# zumy_carrier_board.net
KiCad netlist of a schematic drawn in EAGLE
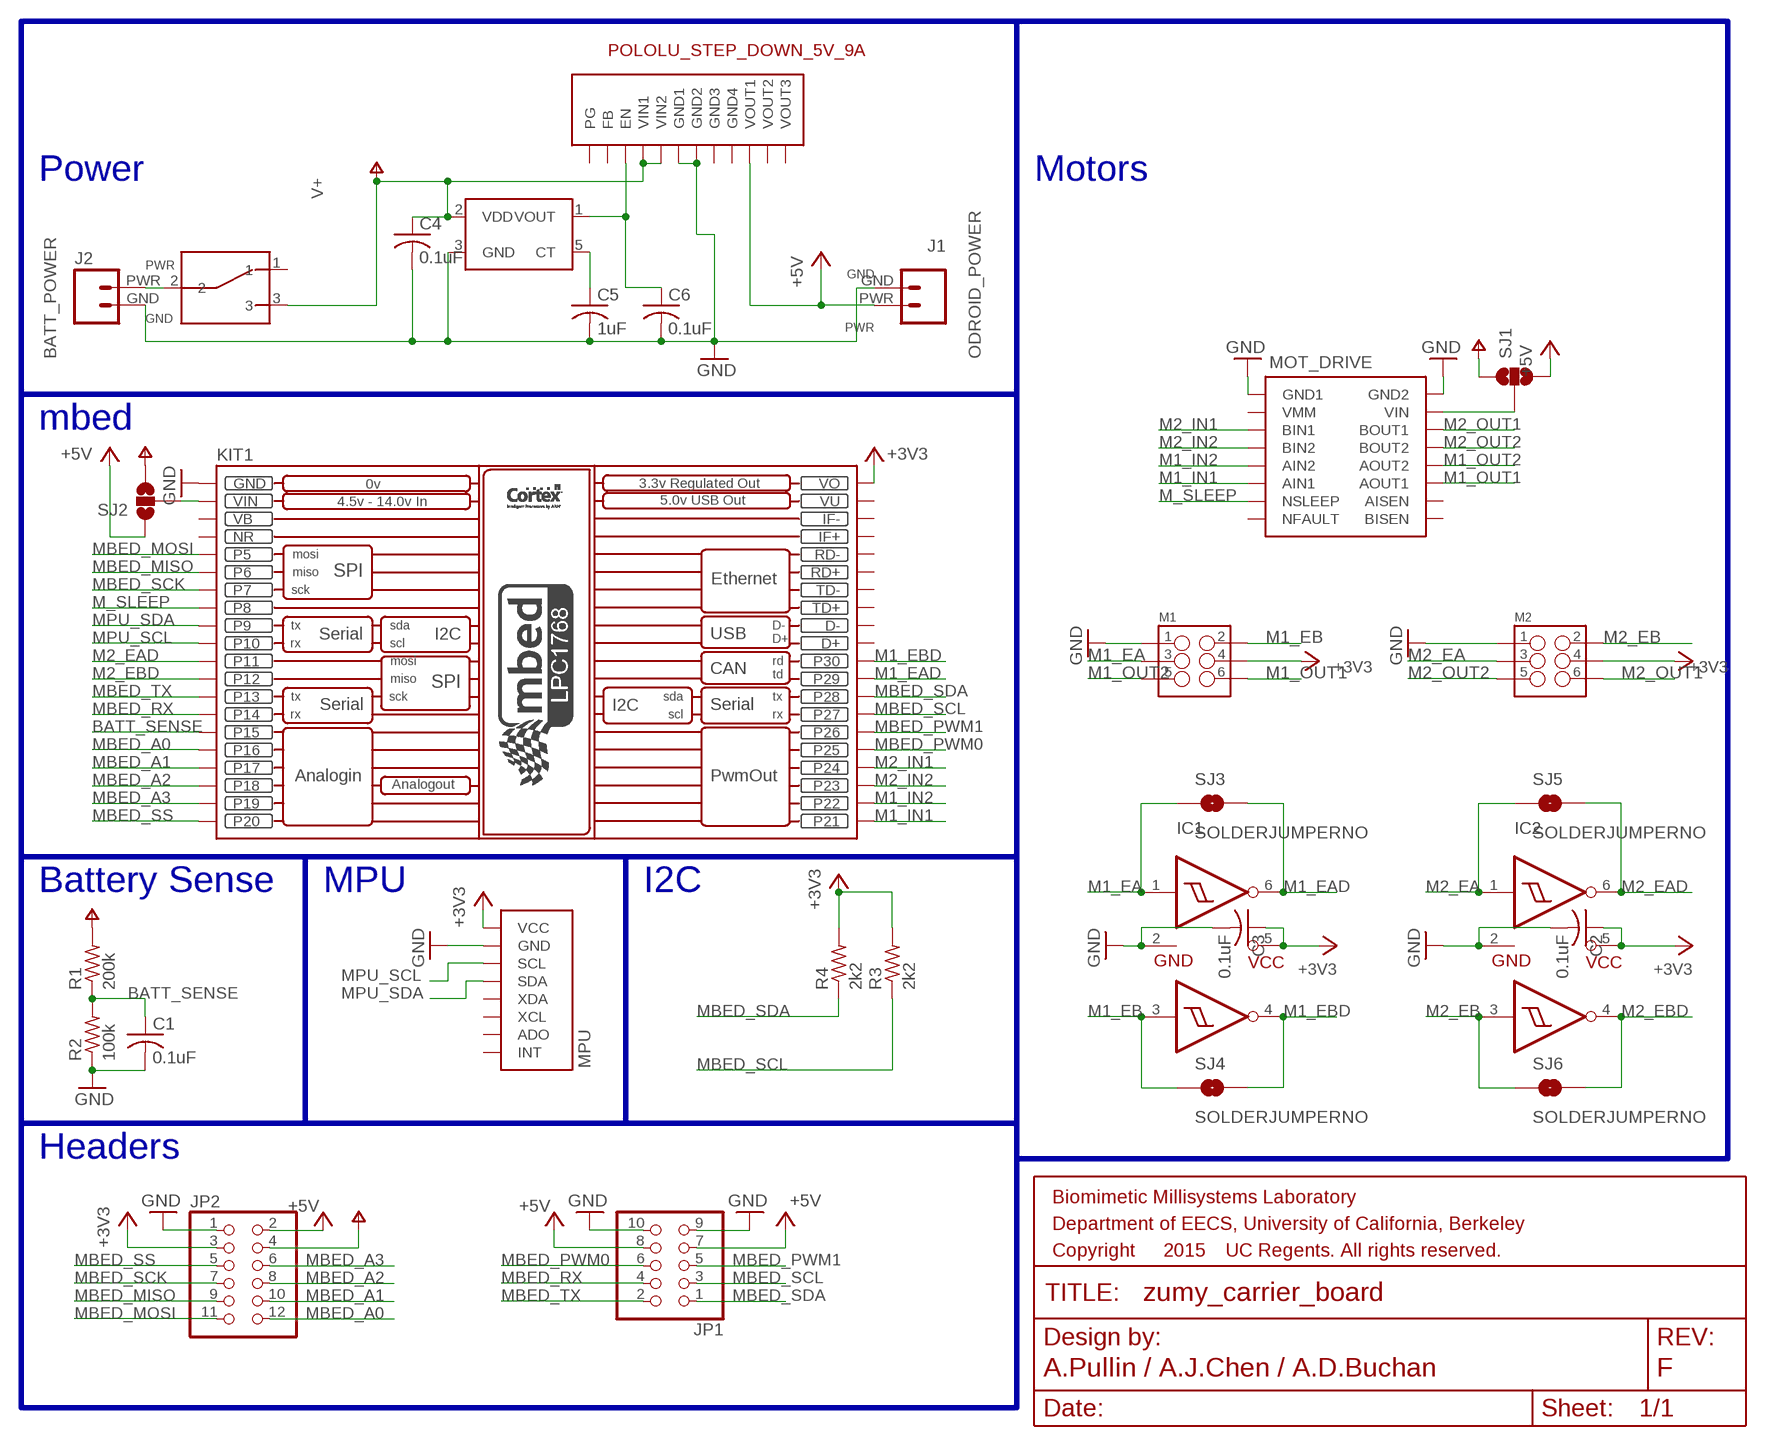
[diagram p0: schematic, sheet 1]

(export (version "E")
  (design (tool "Eeschema 10.0.6"))
  (components
    (comp (ref "C1")
      (value "0.1uF")
      (footprint "eagle-import:C1206")
      (libsource (lib "eagle-import") (part "C-USC1206"))
    )
    (comp (ref "C2")
      (value "0.1uF")
      (footprint "eagle-import:C1206")
      (libsource (lib "eagle-import") (part "C-USC1206"))
    )
    (comp (ref "C3")
      (value "0.1uF")
      (footprint "eagle-import:C1206")
      (libsource (lib "eagle-import") (part "C-USC1206"))
    )
    (comp (ref "C4")
      (value "0.1uF")
      (footprint "eagle-import:C1206")
      (libsource (lib "eagle-import") (part "C-USC1206"))
    )
    (comp (ref "C5")
      (value "1uF")
      (footprint "eagle-import:C1206")
      (libsource (lib "eagle-import") (part "C-USC1206"))
    )
    (comp (ref "C6")
      (value "0.1uF")
      (footprint "eagle-import:C1206")
      (libsource (lib "eagle-import") (part "C-USC1206"))
    )
    (comp (ref "IC1")
      (value "SN74AUP2G17")
      (footprint "eagle-import:SC-70-6")
      (libsource (lib "eagle-import") (part "SN74AUP2G17"))
    )
    (comp (ref "IC2")
      (value "SN74AUP2G17")
      (footprint "eagle-import:SC-70-6")
      (libsource (lib "eagle-import") (part "SN74AUP2G17"))
    )
    (comp (ref "J1")
      (value "ODROID_POWER")
      (footprint "eagle-import:ODOIRD_PWR")
      (libsource (lib "eagle-import") (part "ODROID_POWER"))
    )
    (comp (ref "J2")
      (value "BATT_POWER")
      (footprint "eagle-import:BATT_POWER")
      (libsource (lib "eagle-import") (part "BATT_POWER"))
    )
    (comp (ref "JP1")
      (value "PINHD-2X5")
      (footprint "eagle-import:2X05")
      (libsource (lib "eagle-import") (part "PINHD-2X5"))
    )
    (comp (ref "JP2")
      (value "PINHD-2X6")
      (footprint "eagle-import:2X06")
      (libsource (lib "eagle-import") (part "PINHD-2X6"))
    )
    (comp (ref "KIT1")
      (value "MBED_NXP_LPC1768")
      (footprint "eagle-import:MBED-KIT")
      (libsource (lib "eagle-import") (part "MBED_NXP_LPC1768"))
    )
    (comp (ref "M1")
      (value "M03X2SHROUD")
      (footprint "eagle-import:2X3-SHROUDED")
      (libsource (lib "eagle-import") (part "M03X2SHROUD"))
    )
    (comp (ref "M2")
      (value "M03X2SHROUD")
      (footprint "eagle-import:2X3-SHROUDED")
      (libsource (lib "eagle-import") (part "M03X2SHROUD"))
    )
    (comp (ref "MOT_DRIVE")
      (value "POLOLU_DRV8833_MODULE")
      (footprint "eagle-import:POLOLU_DRV8833_MODULE")
      (libsource (lib "eagle-import") (part "POLOLU_DRV8833_MODULE"))
    )
    (comp (ref "MPU")
      (value "ITG/MPU_MODULE")
      (footprint "eagle-import:ITG_MPU_MODULE")
      (libsource (lib "eagle-import") (part "ITG/MPU_MODULE"))
    )
    (comp (ref "R1")
      (value "200k")
      (footprint "eagle-import:R1206")
      (libsource (lib "eagle-import") (part "R-US_R1206"))
    )
    (comp (ref "R2")
      (value "100k")
      (footprint "eagle-import:R1206")
      (libsource (lib "eagle-import") (part "R-US_R1206"))
    )
    (comp (ref "R3")
      (value "2k2")
      (footprint "eagle-import:R1206")
      (libsource (lib "eagle-import") (part "R-US_R1206"))
    )
    (comp (ref "R4")
      (value "2k2")
      (footprint "eagle-import:R1206")
      (libsource (lib "eagle-import") (part "R-US_R1206"))
    )
    (comp (ref "SJ1")
      (value "SOLDERJUMPER_2WAYT")
      (footprint "eagle-import:SJ_2")
      (libsource (lib "eagle-import") (part "SOLDERJUMPER_2WAYT"))
    )
    (comp (ref "SJ2")
      (value "SOLDERJUMPER_2WAYT")
      (footprint "eagle-import:SJ_2")
      (libsource (lib "eagle-import") (part "SOLDERJUMPER_2WAYT"))
    )
    (comp (ref "SJ3")
      (value "SOLDERJUMPERNO")
      (footprint "eagle-import:SJ_2S-NO")
      (libsource (lib "eagle-import") (part "SOLDERJUMPERNO"))
    )
    (comp (ref "SJ4")
      (value "SOLDERJUMPERNO")
      (footprint "eagle-import:SJ_2S-NO")
      (libsource (lib "eagle-import") (part "SOLDERJUMPERNO"))
    )
    (comp (ref "SJ5")
      (value "SOLDERJUMPERNO")
      (footprint "eagle-import:SJ_2S-NO")
      (libsource (lib "eagle-import") (part "SOLDERJUMPERNO"))
    )
    (comp (ref "SJ6")
      (value "SOLDERJUMPERNO")
      (footprint "eagle-import:SJ_2S-NO")
      (libsource (lib "eagle-import") (part "SOLDERJUMPERNO"))
    )
    (comp (ref "SW1")
      (value "500SSP1S1M6QEA")
      (footprint "eagle-import:500SSP1S1M6QEA_SWITCH")
      (libsource (lib "eagle-import") (part "500SSP1S1M6QEA"))
    )
    (comp (ref "U$2")
      (value "BD5260G")
      (footprint "eagle-import:SOT23-5")
      (libsource (lib "eagle-import") (part "BD5260G"))
    )
    (comp (ref "U$3")
      (value "POLOLU_STEP_DOWN_5V_9A")
      (footprint "eagle-import:POLOLU_STEP_DOWN_5V_9A")
      (libsource (lib "eagle-import") (part "POLOLU_STEP_DOWN_5V_9A"))
    )
  )
  (nets
    (net (code "1") (name "+3V3") (class "Default")
      (node (ref "C2") (pin "1") (pinfunction "1_1") (pintype "passive"))
      (node (ref "C3") (pin "1") (pinfunction "1_1") (pintype "passive"))
      (node (ref "IC1") (pin "5") (pinfunction "VCC_5") (pintype "output"))
      (node (ref "IC2") (pin "5") (pinfunction "VCC_5") (pintype "output"))
      (node (ref "JP2") (pin "3") (pinfunction "3_3") (pintype "passive"))
      (node (ref "KIT1") (pin "VOUT") (pinfunction "VO_VOUT") (pintype "power_in"))
      (node (ref "M1") (pin "4") (pinfunction "4_4") (pintype "bidirectional"))
      (node (ref "M2") (pin "4") (pinfunction "4_4") (pintype "bidirectional"))
      (node (ref "MPU") (pin "VCC") (pinfunction "VCC_VCC") (pintype "bidirectional"))
      (node (ref "R3") (pin "2") (pinfunction "2_2") (pintype "passive"))
      (node (ref "R4") (pin "2") (pinfunction "2_2") (pintype "passive"))
    )
    (net (code "2") (name "+5V") (class "Default")
      (node (ref "J1") (pin "PWR") (pinfunction "PWR_PWR") (pintype "passive"))
      (node (ref "JP1") (pin "7") (pinfunction "7_7") (pintype "passive"))
      (node (ref "JP1") (pin "8") (pinfunction "8_8") (pintype "passive"))
      (node (ref "JP2") (pin "2") (pinfunction "2_2") (pintype "passive"))
      (node (ref "SJ1") (pin "3") (pinfunction "3_3") (pintype "passive"))
      (node (ref "SJ2") (pin "1") (pinfunction "1_1") (pintype "passive"))
      (node (ref "U$3") (pin "VOUT1") (pinfunction "VOUT1_VOUT1") (pintype "bidirectional"))
    )
    (net (code "3") (name "/BATT_SENSE") (class "Default")
      (node (ref "C1") (pin "1") (pinfunction "1_1") (pintype "passive"))
      (node (ref "KIT1") (pin "P$15") (pinfunction "P15_P$15") (pintype "bidirectional"))
      (node (ref "R1") (pin "1") (pinfunction "1_1") (pintype "passive"))
      (node (ref "R2") (pin "2") (pinfunction "2_2") (pintype "passive"))
    )
    (net (code "4") (name "/M1_EA") (class "Default")
      (node (ref "IC1") (pin "1") (pinfunction "1A_1") (pintype "input"))
      (node (ref "M1") (pin "3") (pinfunction "3_3") (pintype "bidirectional"))
      (node (ref "SJ3") (pin "1") (pinfunction "1_1") (pintype "passive"))
    )
    (net (code "5") (name "/M1_EAD") (class "Default")
      (node (ref "IC1") (pin "6") (pinfunction "1Y_6") (pintype "output"))
      (node (ref "KIT1") (pin "P$29") (pinfunction "P29_P$29") (pintype "bidirectional"))
      (node (ref "SJ3") (pin "2") (pinfunction "2_2") (pintype "passive"))
    )
    (net (code "6") (name "/M1_EB") (class "Default")
      (node (ref "IC1") (pin "3") (pinfunction "2A_3") (pintype "input"))
      (node (ref "M1") (pin "2") (pinfunction "2_2") (pintype "bidirectional"))
      (node (ref "SJ4") (pin "1") (pinfunction "1_1") (pintype "passive"))
    )
    (net (code "7") (name "/M1_EBD") (class "Default")
      (node (ref "IC1") (pin "4") (pinfunction "2Y_4") (pintype "output"))
      (node (ref "KIT1") (pin "P$30") (pinfunction "P30_P$30") (pintype "bidirectional"))
      (node (ref "SJ4") (pin "2") (pinfunction "2_2") (pintype "passive"))
    )
    (net (code "8") (name "/M1_IN1") (class "Default")
      (node (ref "KIT1") (pin "P$21") (pinfunction "P21_P$21") (pintype "bidirectional"))
      (node (ref "MOT_DRIVE") (pin "AIN1") (pinfunction "AIN1_AIN1") (pintype "bidirectional"))
    )
    (net (code "9") (name "/M1_IN2") (class "Default")
      (node (ref "KIT1") (pin "P$22") (pinfunction "P22_P$22") (pintype "bidirectional"))
      (node (ref "MOT_DRIVE") (pin "AIN2") (pinfunction "AIN2_AIN2") (pintype "bidirectional"))
    )
    (net (code "10") (name "/M1_OUT1") (class "Default")
      (node (ref "M1") (pin "6") (pinfunction "6_6") (pintype "bidirectional"))
      (node (ref "MOT_DRIVE") (pin "AOUT1") (pinfunction "AOUT1_AOUT1") (pintype "bidirectional"))
    )
    (net (code "11") (name "/M1_OUT2") (class "Default")
      (node (ref "M1") (pin "5") (pinfunction "5_5") (pintype "bidirectional"))
      (node (ref "MOT_DRIVE") (pin "AOUT2") (pinfunction "AOUT2_AOUT2") (pintype "bidirectional"))
    )
    (net (code "12") (name "/M2_EA") (class "Default")
      (node (ref "IC2") (pin "1") (pinfunction "1A_1") (pintype "input"))
      (node (ref "M2") (pin "3") (pinfunction "3_3") (pintype "bidirectional"))
      (node (ref "SJ5") (pin "1") (pinfunction "1_1") (pintype "passive"))
    )
    (net (code "13") (name "/M2_EAD") (class "Default")
      (node (ref "IC2") (pin "6") (pinfunction "1Y_6") (pintype "output"))
      (node (ref "KIT1") (pin "P$11") (pinfunction "P11_P$11") (pintype "bidirectional"))
      (node (ref "SJ5") (pin "2") (pinfunction "2_2") (pintype "passive"))
    )
    (net (code "14") (name "/M2_EB") (class "Default")
      (node (ref "IC2") (pin "3") (pinfunction "2A_3") (pintype "input"))
      (node (ref "M2") (pin "2") (pinfunction "2_2") (pintype "bidirectional"))
      (node (ref "SJ6") (pin "1") (pinfunction "1_1") (pintype "passive"))
    )
    (net (code "15") (name "/M2_EBD") (class "Default")
      (node (ref "IC2") (pin "4") (pinfunction "2Y_4") (pintype "output"))
      (node (ref "KIT1") (pin "P$12") (pinfunction "P12_P$12") (pintype "bidirectional"))
      (node (ref "SJ6") (pin "2") (pinfunction "2_2") (pintype "passive"))
    )
    (net (code "16") (name "/M2_IN1") (class "Default")
      (node (ref "KIT1") (pin "P$24") (pinfunction "P24_P$24") (pintype "bidirectional"))
      (node (ref "MOT_DRIVE") (pin "BIN1") (pinfunction "BIN1_BIN1") (pintype "bidirectional"))
    )
    (net (code "17") (name "/M2_IN2") (class "Default")
      (node (ref "KIT1") (pin "P$23") (pinfunction "P23_P$23") (pintype "bidirectional"))
      (node (ref "MOT_DRIVE") (pin "BIN2") (pinfunction "BIN2_BIN2") (pintype "bidirectional"))
    )
    (net (code "18") (name "/M2_OUT1") (class "Default")
      (node (ref "M2") (pin "6") (pinfunction "6_6") (pintype "bidirectional"))
      (node (ref "MOT_DRIVE") (pin "BOUT1") (pinfunction "BOUT1_BOUT1") (pintype "bidirectional"))
    )
    (net (code "19") (name "/M2_OUT2") (class "Default")
      (node (ref "M2") (pin "5") (pinfunction "5_5") (pintype "bidirectional"))
      (node (ref "MOT_DRIVE") (pin "BOUT2") (pinfunction "BOUT2_BOUT2") (pintype "bidirectional"))
    )
    (net (code "20") (name "/MBED_A0") (class "Default")
      (node (ref "JP2") (pin "12") (pinfunction "12_12") (pintype "passive"))
      (node (ref "KIT1") (pin "P$16") (pinfunction "P16_P$16") (pintype "bidirectional"))
    )
    (net (code "21") (name "/MBED_A1") (class "Default")
      (node (ref "JP2") (pin "10") (pinfunction "10_10") (pintype "passive"))
      (node (ref "KIT1") (pin "P$17") (pinfunction "P17_P$17") (pintype "bidirectional"))
    )
    (net (code "22") (name "/MBED_A2") (class "Default")
      (node (ref "JP2") (pin "8") (pinfunction "8_8") (pintype "passive"))
      (node (ref "KIT1") (pin "P$18") (pinfunction "P18_P$18") (pintype "bidirectional"))
    )
    (net (code "23") (name "/MBED_A3") (class "Default")
      (node (ref "JP2") (pin "6") (pinfunction "6_6") (pintype "passive"))
      (node (ref "KIT1") (pin "P$19") (pinfunction "P19_P$19") (pintype "bidirectional"))
    )
    (net (code "24") (name "/MBED_MISO") (class "Default")
      (node (ref "JP2") (pin "9") (pinfunction "9_9") (pintype "passive"))
      (node (ref "KIT1") (pin "P$6") (pinfunction "P6_P$6") (pintype "bidirectional"))
    )
    (net (code "25") (name "/MBED_MOSI") (class "Default")
      (node (ref "JP2") (pin "11") (pinfunction "11_11") (pintype "passive"))
      (node (ref "KIT1") (pin "P$5") (pinfunction "P5_P$5") (pintype "bidirectional"))
    )
    (net (code "26") (name "/MBED_PWM0") (class "Default")
      (node (ref "JP1") (pin "6") (pinfunction "6_6") (pintype "passive"))
      (node (ref "KIT1") (pin "P$25") (pinfunction "P25_P$25") (pintype "bidirectional"))
    )
    (net (code "27") (name "/MBED_PWM1") (class "Default")
      (node (ref "JP1") (pin "5") (pinfunction "5_5") (pintype "passive"))
      (node (ref "KIT1") (pin "P$26") (pinfunction "P26_P$26") (pintype "bidirectional"))
    )
    (net (code "28") (name "/MBED_RX") (class "Default")
      (node (ref "JP1") (pin "4") (pinfunction "4_4") (pintype "passive"))
      (node (ref "KIT1") (pin "P$14") (pinfunction "P14_P$14") (pintype "bidirectional"))
    )
    (net (code "29") (name "/MBED_SCK") (class "Default")
      (node (ref "JP2") (pin "7") (pinfunction "7_7") (pintype "passive"))
      (node (ref "KIT1") (pin "P$7") (pinfunction "P7_P$7") (pintype "bidirectional"))
    )
    (net (code "30") (name "/MBED_SCL") (class "Default")
      (node (ref "JP1") (pin "3") (pinfunction "3_3") (pintype "passive"))
      (node (ref "KIT1") (pin "P$27") (pinfunction "P27_P$27") (pintype "bidirectional"))
      (node (ref "R3") (pin "1") (pinfunction "1_1") (pintype "passive"))
    )
    (net (code "31") (name "/MBED_SDA") (class "Default")
      (node (ref "JP1") (pin "1") (pinfunction "1_1") (pintype "passive"))
      (node (ref "KIT1") (pin "P$28") (pinfunction "P28_P$28") (pintype "bidirectional"))
      (node (ref "R4") (pin "1") (pinfunction "1_1") (pintype "passive"))
    )
    (net (code "32") (name "/MBED_SS") (class "Default")
      (node (ref "JP2") (pin "5") (pinfunction "5_5") (pintype "passive"))
      (node (ref "KIT1") (pin "P$20") (pinfunction "P20_P$20") (pintype "bidirectional"))
    )
    (net (code "33") (name "/MBED_TX") (class "Default")
      (node (ref "JP1") (pin "2") (pinfunction "2_2") (pintype "passive"))
      (node (ref "KIT1") (pin "P$13") (pinfunction "P13_P$13") (pintype "bidirectional"))
    )
    (net (code "34") (name "/MPU_SCL") (class "Default")
      (node (ref "KIT1") (pin "P$10") (pinfunction "P10_P$10") (pintype "bidirectional"))
      (node (ref "MPU") (pin "SCL") (pinfunction "SCL_SCL") (pintype "bidirectional"))
    )
    (net (code "35") (name "/MPU_SDA") (class "Default")
      (node (ref "KIT1") (pin "P$9") (pinfunction "P9_P$9") (pintype "bidirectional"))
      (node (ref "MPU") (pin "SDA") (pinfunction "SDA_SDA") (pintype "bidirectional"))
    )
    (net (code "36") (name "/M_SLEEP") (class "Default")
      (node (ref "KIT1") (pin "P$8") (pinfunction "P8_P$8") (pintype "bidirectional"))
      (node (ref "MOT_DRIVE") (pin "NSLEEP") (pinfunction "NSLEEP_NSLEEP") (pintype "bidirectional"))
    )
    (net (code "37") (name "/NR") (class "Default")
      (node (ref "KIT1") (pin "NR") (pinfunction "NR_NR") (pintype "power_in"))
    )
    (net (code "38") (name "/VB") (class "Default")
      (node (ref "KIT1") (pin "VB") (pinfunction "VB_VB") (pintype "power_in"))
    )
    (net (code "39") (name "/VU") (class "Default")
      (node (ref "KIT1") (pin "VU") (pinfunction "VU_VU") (pintype "power_in"))
    )
    (net (code "40") (name "GND") (class "Default")
      (node (ref "C1") (pin "2") (pinfunction "2_2") (pintype "passive"))
      (node (ref "C2") (pin "2") (pinfunction "2_2") (pintype "passive"))
      (node (ref "C3") (pin "2") (pinfunction "2_2") (pintype "passive"))
      (node (ref "C4") (pin "2") (pinfunction "2_2") (pintype "passive"))
      (node (ref "C5") (pin "2") (pinfunction "2_2") (pintype "passive"))
      (node (ref "C6") (pin "2") (pinfunction "2_2") (pintype "passive"))
      (node (ref "IC1") (pin "2") (pinfunction "GND_2") (pintype "input"))
      (node (ref "IC2") (pin "2") (pinfunction "GND_2") (pintype "input"))
      (node (ref "J1") (pin "GND") (pinfunction "GND_GND") (pintype "passive"))
      (node (ref "J2") (pin "GND") (pinfunction "GND_GND") (pintype "passive"))
      (node (ref "JP1") (pin "10") (pinfunction "10_10") (pintype "passive"))
      (node (ref "JP1") (pin "9") (pinfunction "9_9") (pintype "passive"))
      (node (ref "JP2") (pin "1") (pinfunction "1_1") (pintype "passive"))
      (node (ref "KIT1") (pin "GND") (pinfunction "GND_GND") (pintype "power_in"))
      (node (ref "M1") (pin "1") (pinfunction "1_1") (pintype "bidirectional"))
      (node (ref "M2") (pin "1") (pinfunction "1_1") (pintype "bidirectional"))
      (node (ref "MOT_DRIVE") (pin "GND1") (pinfunction "GND1_GND1") (pintype "bidirectional"))
      (node (ref "MOT_DRIVE") (pin "GND2") (pinfunction "GND2_GND2") (pintype "bidirectional"))
      (node (ref "MPU") (pin "GND") (pinfunction "GND_GND") (pintype "bidirectional"))
      (node (ref "R2") (pin "1") (pinfunction "1_1") (pintype "passive"))
      (node (ref "U$2") (pin "3") (pinfunction "GND_3") (pintype "bidirectional"))
      (node (ref "U$3") (pin "GND1") (pinfunction "GND1_GND1") (pintype "bidirectional"))
      (node (ref "U$3") (pin "GND2") (pinfunction "GND2_GND2") (pintype "bidirectional"))
    )
    (net (code "41") (name "Net-(J2-PadPWR)") (class "Default")
      (node (ref "J2") (pin "PWR") (pinfunction "PWR_PWR") (pintype "passive"))
      (node (ref "SW1") (pin "2") (pinfunction "2_2") (pintype "bidirectional"))
    )
    (net (code "42") (name "Net-(KIT1-PadVIN)") (class "Default")
      (node (ref "KIT1") (pin "VIN") (pinfunction "VIN_VIN") (pintype "power_in"))
      (node (ref "SJ2") (pin "2") (pinfunction "2_2") (pintype "passive"))
    )
    (net (code "43") (name "Net-(MOT_DRIVE-PadVIN)") (class "Default")
      (node (ref "MOT_DRIVE") (pin "VIN") (pinfunction "VIN_VIN") (pintype "bidirectional"))
      (node (ref "SJ1") (pin "2") (pinfunction "2_2") (pintype "passive"))
    )
    (net (code "44") (name "Net-(U$2-CT)") (class "Default")
      (node (ref "C5") (pin "1") (pinfunction "1_1") (pintype "passive"))
      (node (ref "U$2") (pin "5") (pinfunction "CT_5") (pintype "bidirectional"))
    )
    (net (code "45") (name "Net-(U$2-VOUT)") (class "Default")
      (node (ref "C6") (pin "1") (pinfunction "1_1") (pintype "passive"))
      (node (ref "U$2") (pin "1") (pinfunction "VOUT_1") (pintype "bidirectional"))
      (node (ref "U$3") (pin "EN") (pinfunction "EN_EN") (pintype "bidirectional"))
    )
    (net (code "46") (name "V+") (class "Default")
      (node (ref "C4") (pin "1") (pinfunction "1_1") (pintype "passive"))
      (node (ref "JP2") (pin "4") (pinfunction "4_4") (pintype "passive"))
      (node (ref "R1") (pin "2") (pinfunction "2_2") (pintype "passive"))
      (node (ref "SJ1") (pin "1") (pinfunction "1_1") (pintype "passive"))
      (node (ref "SJ2") (pin "3") (pinfunction "3_3") (pintype "passive"))
      (node (ref "SW1") (pin "3") (pinfunction "3_3") (pintype "bidirectional"))
      (node (ref "U$2") (pin "2") (pinfunction "VDD_2") (pintype "bidirectional"))
      (node (ref "U$3") (pin "VIN1") (pinfunction "VIN1_VIN1") (pintype "bidirectional"))
      (node (ref "U$3") (pin "VIN2") (pinfunction "VIN2_VIN2") (pintype "bidirectional"))
    )
    (net (code "47") (name "unconnected-(KIT1-PadD+)") (class "Default")
      (node (ref "KIT1") (pin "D+") (pinfunction "D+_D+") (pintype "bidirectional"))
    )
    (net (code "48") (name "unconnected-(KIT1-PadD-)") (class "Default")
      (node (ref "KIT1") (pin "D-") (pinfunction "D-_D-") (pintype "bidirectional"))
    )
    (net (code "49") (name "unconnected-(KIT1-PadIF+)") (class "Default")
      (node (ref "KIT1") (pin "IF+") (pinfunction "IF+_IF+") (pintype "bidirectional"))
    )
    (net (code "50") (name "unconnected-(KIT1-PadIF-)") (class "Default")
      (node (ref "KIT1") (pin "IF-") (pinfunction "IF-_IF-") (pintype "bidirectional"))
    )
    (net (code "51") (name "unconnected-(KIT1-PadRD+)") (class "Default")
      (node (ref "KIT1") (pin "RD+") (pinfunction "RD+_RD+") (pintype "bidirectional"))
    )
    (net (code "52") (name "unconnected-(KIT1-PadRD-)") (class "Default")
      (node (ref "KIT1") (pin "RD-") (pinfunction "RD-_RD-") (pintype "bidirectional"))
    )
    (net (code "53") (name "unconnected-(KIT1-PadTD+)") (class "Default")
      (node (ref "KIT1") (pin "TD+") (pinfunction "TD+_TD+") (pintype "bidirectional"))
    )
    (net (code "54") (name "unconnected-(KIT1-PadTD-)") (class "Default")
      (node (ref "KIT1") (pin "TD-") (pinfunction "TD-_TD-") (pintype "bidirectional"))
    )
    (net (code "55") (name "unconnected-(MOT_DRIVE-PadAISEN)") (class "Default")
      (node (ref "MOT_DRIVE") (pin "AISEN") (pinfunction "AISEN_AISEN") (pintype "bidirectional"))
    )
    (net (code "56") (name "unconnected-(MOT_DRIVE-PadBISEN)") (class "Default")
      (node (ref "MOT_DRIVE") (pin "BISEN") (pinfunction "BISEN_BISEN") (pintype "bidirectional"))
    )
    (net (code "57") (name "unconnected-(MOT_DRIVE-PadNFAULT)") (class "Default")
      (node (ref "MOT_DRIVE") (pin "NFAULT") (pinfunction "NFAULT_NFAULT") (pintype "bidirectional"))
    )
    (net (code "58") (name "unconnected-(MOT_DRIVE-PadVMM)") (class "Default")
      (node (ref "MOT_DRIVE") (pin "VMM") (pinfunction "VMM_VMM") (pintype "bidirectional"))
    )
    (net (code "59") (name "unconnected-(MPU-PadADO)") (class "Default")
      (node (ref "MPU") (pin "ADO") (pinfunction "ADO_ADO") (pintype "bidirectional"))
    )
    (net (code "60") (name "unconnected-(MPU-PadINT)") (class "Default")
      (node (ref "MPU") (pin "INT") (pinfunction "INT_INT") (pintype "bidirectional"))
    )
    (net (code "61") (name "unconnected-(MPU-PadXCL)") (class "Default")
      (node (ref "MPU") (pin "XCL") (pinfunction "XCL_XCL") (pintype "bidirectional"))
    )
    (net (code "62") (name "unconnected-(MPU-PadXDA)") (class "Default")
      (node (ref "MPU") (pin "XDA") (pinfunction "XDA_XDA") (pintype "bidirectional"))
    )
    (net (code "63") (name "unconnected-(SW1-Pad1)") (class "Default")
      (node (ref "SW1") (pin "1") (pinfunction "1_1") (pintype "bidirectional"))
    )
    (net (code "64") (name "unconnected-(U$3-PadFB)") (class "Default")
      (node (ref "U$3") (pin "FB") (pinfunction "FB_FB") (pintype "bidirectional"))
    )
    (net (code "65") (name "unconnected-(U$3-PadGND3)") (class "Default")
      (node (ref "U$3") (pin "GND3") (pinfunction "GND3_GND3") (pintype "bidirectional"))
    )
    (net (code "66") (name "unconnected-(U$3-PadGND4)") (class "Default")
      (node (ref "U$3") (pin "GND4") (pinfunction "GND4_GND4") (pintype "bidirectional"))
    )
    (net (code "67") (name "unconnected-(U$3-PadPG)") (class "Default")
      (node (ref "U$3") (pin "PG") (pinfunction "PG_PG") (pintype "bidirectional"))
    )
    (net (code "68") (name "unconnected-(U$3-PadVOUT2)") (class "Default")
      (node (ref "U$3") (pin "VOUT2") (pinfunction "VOUT2_VOUT2") (pintype "bidirectional"))
    )
    (net (code "69") (name "unconnected-(U$3-PadVOUT3)") (class "Default")
      (node (ref "U$3") (pin "VOUT3") (pinfunction "VOUT3_VOUT3") (pintype "bidirectional"))
    )
  )
)
